# Sheet_Power.net
KiCad netlist of a schematic drawn in Altium Designer
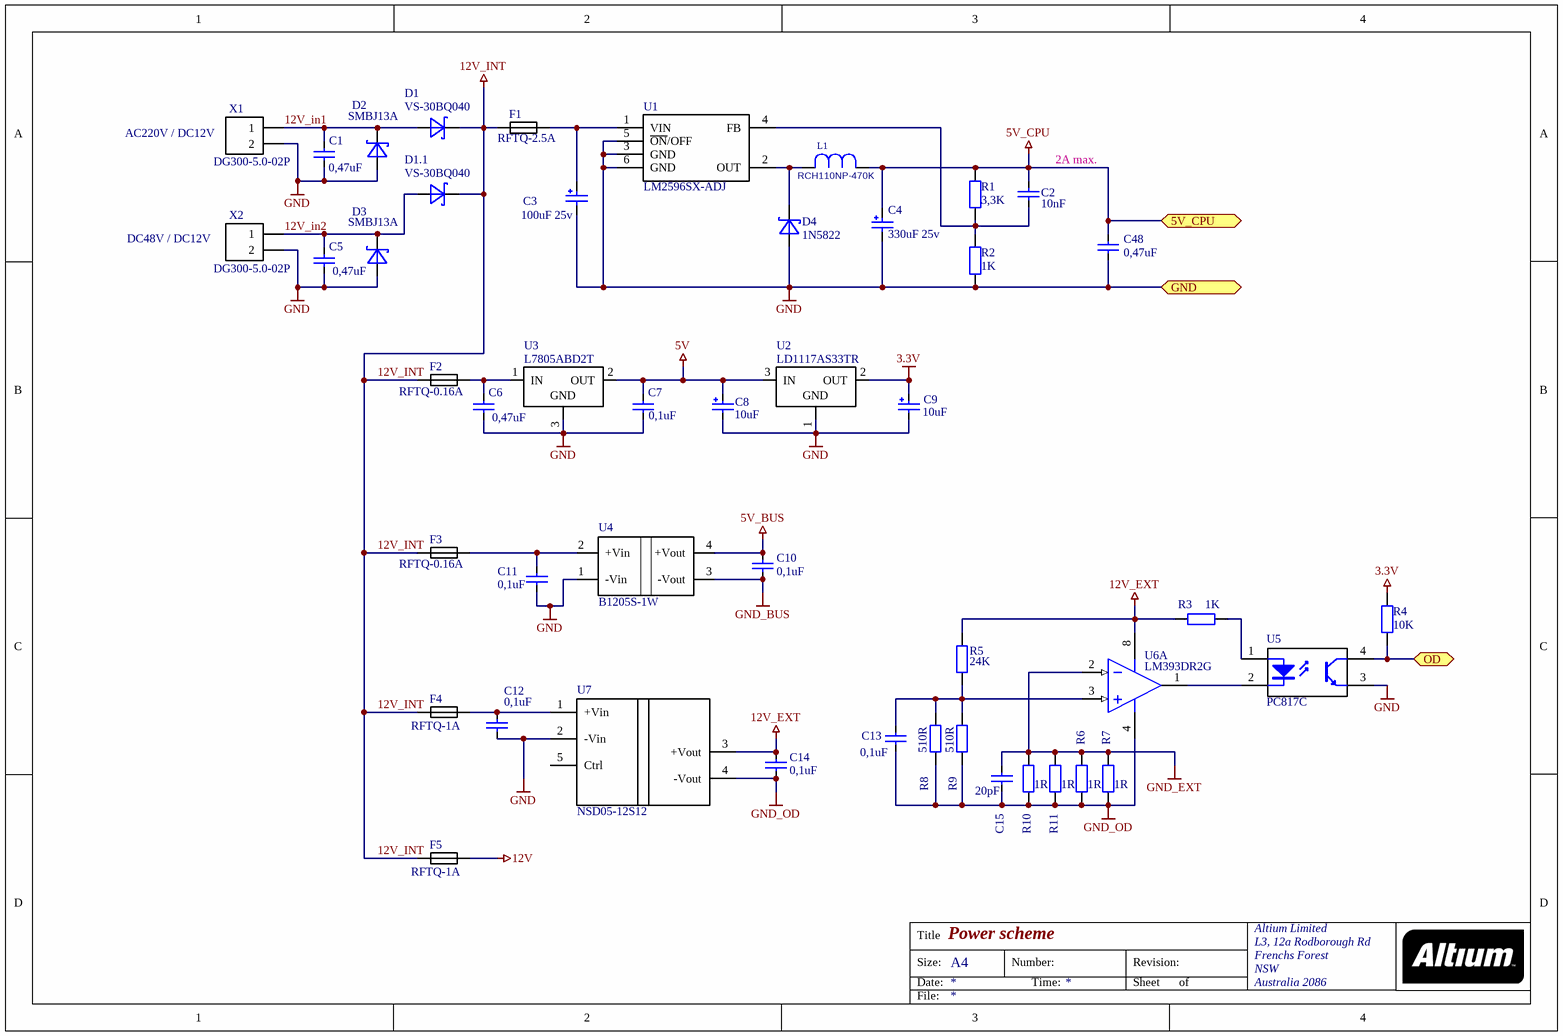
[diagram p0: Sheet_Power.SchDoc]

(export (version "E")
  (design (tool "Eeschema 10.0.6"))
  (components
    (comp (ref "C1")
      (value "0,47uF")
      (footprint "C_1206")
      (description "Capacitor semi")
      (fields (field (name "Comment") "Cap_Semi"))
      (libsource (lib "Capacitor") (part "Cap_Semi"))
    )
    (comp (ref "C2")
      (value "10nF")
      (footprint "C_0805")
      (description "Capacitor semi")
      (fields (field (name "Comment") "Cap_Semi"))
      (libsource (lib "Capacitor") (part "Cap_Semi"))
    )
    (comp (ref "C3")
      (value "100uF 25v")
      (footprint "8x11")
      (description "Capacitor Polar")
      (fields (field (name "Comment") "Cap_Polar"))
      (libsource (lib "Capacitor") (part "Cap_Polar"))
    )
    (comp (ref "C4")
      (value "330uF 25v")
      (footprint "10x16")
      (description "Capacitor Polar")
      (fields (field (name "Comment") "Cap_Polar"))
      (libsource (lib "Capacitor") (part "Cap_Polar"))
    )
    (comp (ref "C5")
      (value "0,47uF")
      (footprint "C_1206")
      (description "Capacitor semi")
      (fields (field (name "Comment") "Cap_Semi"))
      (libsource (lib "Capacitor") (part "Cap_Semi"))
    )
    (comp (ref "C6")
      (value "0,47uF")
      (footprint "C_1206")
      (description "Capacitor semi")
      (fields (field (name "Comment") "Cap_Semi"))
      (libsource (lib "Capacitor") (part "Cap_Semi"))
    )
    (comp (ref "C7")
      (value "0,1uF")
      (footprint "C_0805")
      (description "Capacitor semi")
      (fields (field (name "Comment") "Cap_Semi"))
      (libsource (lib "Capacitor") (part "Cap_Semi"))
    )
    (comp (ref "C8")
      (value "10uF")
      (footprint "5x11")
      (description "Capacitor polar")
      (fields (field (name "Comment") "Cap_Polar"))
      (libsource (lib "Capacitor") (part "Capacitor Polar"))
    )
    (comp (ref "C9")
      (value "10uF")
      (footprint "5x11")
      (description "Capacitor polar")
      (fields (field (name "Comment") "Cap_Polar"))
      (libsource (lib "Capacitor") (part "Capacitor Polar"))
    )
    (comp (ref "C10")
      (value "0,1uF")
      (footprint "C_0805")
      (description "Capacitor semi")
      (fields (field (name "Comment") "Cap_Semi"))
      (libsource (lib "Capacitor") (part "Cap_Semi"))
    )
    (comp (ref "C11")
      (value "0,1uF")
      (footprint "C_0805")
      (description "Capacitor semi")
      (fields (field (name "Comment") "Cap_Semi"))
      (libsource (lib "Capacitor") (part "Cap_Semi"))
    )
    (comp (ref "C12")
      (value "0,1uF")
      (footprint "C_0805")
      (description "Capacitor semi")
      (fields (field (name "Comment") "Cap_Semi"))
      (libsource (lib "Capacitor") (part "Cap_Semi"))
    )
    (comp (ref "C13")
      (value "0,1uF")
      (footprint "C_0805")
      (description "Capacitor semi")
      (fields (field (name "Comment") "Cap_Semi"))
      (libsource (lib "Capacitor") (part "Cap_Semi"))
    )
    (comp (ref "C14")
      (value "0,1uF")
      (footprint "C_0805")
      (description "Capacitor semi")
      (fields (field (name "Comment") "Cap_Semi"))
      (libsource (lib "Capacitor") (part "Cap_Semi"))
    )
    (comp (ref "C15")
      (value "20pF")
      (footprint "C_0805")
      (description "Capacitor semi")
      (fields (field (name "Comment") "Cap_Semi"))
      (libsource (lib "Capacitor") (part "Cap_Semi"))
    )
    (comp (ref "C48")
      (value "0,47uF")
      (footprint "C_1206")
      (description "Capacitor semi")
      (fields (field (name "Comment") "Cap_Semi"))
      (libsource (lib "Capacitor") (part "Cap_Semi"))
    )
    (comp (ref "D1")
      (value "VS-30BQ040")
      (footprint "SMC")
      (description "Diode Schottky")
      (libsource (lib "Diode") (part "VS-30BQ040"))
    )
    (comp (ref "D1.1")
      (value "VS-30BQ040")
      (footprint "SMC")
      (description "Diode Schottky")
      (libsource (lib "Diode") (part "VS-30BQ040"))
    )
    (comp (ref "D2")
      (value "SMBJ13A")
      (footprint "SMB")
      (description "Supressor")
      (libsource (lib "Diode") (part "SMBJ13A"))
    )
    (comp (ref "D3")
      (value "SMBJ13A")
      (footprint "SMB")
      (description "Supressor")
      (libsource (lib "Diode") (part "SMBJ13A"))
    )
    (comp (ref "D4")
      (value "1N5822")
      (footprint "DO-201")
      (description "Diode Schottky")
      (libsource (lib "Diode") (part "1N5822"))
    )
    (comp (ref "F1")
      (value "RFTQ-2.5A")
      (footprint "Fuse RFTQ")
      (description "Fuse")
      (libsource (lib "Other") (part "Fuse"))
    )
    (comp (ref "F2")
      (value "RFTQ-0.16A")
      (footprint "Fuse RFTQ")
      (description "Fuse")
      (libsource (lib "Other") (part "Fuse"))
    )
    (comp (ref "F3")
      (value "RFTQ-0.16A")
      (footprint "Fuse RFTQ")
      (description "Fuse")
      (libsource (lib "Other") (part "Fuse"))
    )
    (comp (ref "F4")
      (value "RFTQ-1A")
      (footprint "Fuse RFTQ")
      (description "Fuse")
      (libsource (lib "Other") (part "Fuse"))
    )
    (comp (ref "F5")
      (value "RFTQ-1A")
      (footprint "Fuse RFTQ")
      (description "Fuse")
      (libsource (lib "Other") (part "Fuse"))
    )
    (comp (ref "L1")
      (value "RCH110NP-470K")
      (footprint "RCH-110")
      (description "Inductor")
      (libsource (lib "Induction") (part "Inductor"))
    )
    (comp (ref "R1")
      (value "3,3K")
      (footprint "R_0805")
      (description "Resistor")
      (libsource (lib "Resistors") (part "Resistor"))
    )
    (comp (ref "R2")
      (value "1K")
      (footprint "R_0805")
      (description "Resistor")
      (libsource (lib "Resistors") (part "Resistor"))
    )
    (comp (ref "R3")
      (value "1K")
      (footprint "R_0805")
      (description "Resistor")
      (libsource (lib "") (part "Resistor_1"))
    )
    (comp (ref "R4")
      (value "10K")
      (footprint "R_0805")
      (description "Resistor")
      (libsource (lib "Resistors") (part "Resistor"))
    )
    (comp (ref "R5")
      (value "24K")
      (footprint "R_0805")
      (description "Resistor")
      (libsource (lib "Resistors") (part "Resistor"))
    )
    (comp (ref "R6")
      (value "1R")
      (footprint "R_1206")
      (description "Resistor")
      (libsource (lib "Resistors") (part "Resistor"))
    )
    (comp (ref "R7")
      (value "1R")
      (footprint "R_1206")
      (description "Resistor")
      (libsource (lib "Resistors") (part "Resistor"))
    )
    (comp (ref "R8")
      (value "510R")
      (footprint "R_0805")
      (description "Resistor")
      (libsource (lib "Resistors") (part "Resistor"))
    )
    (comp (ref "R9")
      (value "510R")
      (footprint "R_0805")
      (description "Resistor")
      (libsource (lib "Resistors") (part "Resistor"))
    )
    (comp (ref "R10")
      (value "1R")
      (footprint "R_1206")
      (description "Resistor")
      (libsource (lib "Resistors") (part "Resistor"))
    )
    (comp (ref "R11")
      (value "1R")
      (footprint "R_1206")
      (description "Resistor")
      (libsource (lib "Resistors") (part "Resistor"))
    )
    (comp (ref "U1")
      (value "LM2596SX-ADJ")
      (footprint "D2PAK_5p")
      (description "Easy Switcher 3.0A Step-Down Voltage Regulator")
      (libsource (lib "Power") (part "LM2596SX-ADJ"))
    )
    (comp (ref "U2")
      (value "LD1117AS33TR")
      (footprint "SOT-223_N")
      (description "Voltage Regulators 800mA")
      (libsource (lib "Power") (part "LD1117AS33TR"))
    )
    (comp (ref "U3")
      (value "L7805ABD2T")
      (footprint "D2PAK_3p")
      (description "Voltage Regulators")
      (libsource (lib "Power") (part "L7805ABD2T"))
    )
    (comp (ref "U4")
      (value "B1205S-1W")
      (footprint "SIP4")
      (description "DC/DC converter")
      (libsource (lib "Power") (part "B0505S-1W"))
    )
    (comp (ref "U5")
      (value "PC817C")
      (footprint "DIP-4")
      (description "Optocoupler")
      (libsource (lib "Chip_Packaging") (part "PC817"))
    )
    (comp (ref "U6")
      (value "LM393DR2G")
      (footprint "SO-8_L")
      (description "Dual Comparators")
      (libsource (lib "Chip_Packaging") (part "LM393DR2G"))
    )
    (comp (ref "U7")
      (value "NSD05-12S12")
      (footprint "NSD05")
      (description "DC/DC Regulated Single Output")
      (libsource (lib "Power") (part "NSD05-12S12"))
    )
    (comp (ref "X1")
      (value "DG300-5.0-02P")
      (footprint "5mm 2")
      (description "Connector 5mm")
      (fields (field (name "ALTIUM_UNNAMED_1") "DG300-5.0-02P"))
      (libsource (lib "Connect") (part "DG300_2pin"))
    )
    (comp (ref "X2")
      (value "DG300-5.0-02P")
      (footprint "5mm 2")
      (description "Connector 5mm")
      (fields (field (name "ALTIUM_UNNAMED_1") "DG300-5.0-02P"))
      (libsource (lib "Connect") (part "DG300_2pin"))
    )
  )
  (nets
    (net (code "1") (name "/12V_in1") (class "Default")
      (node (ref "C1") (pin "2") (pinfunction "2_2") (pintype "passive"))
      (node (ref "D1") (pin "1") (pinfunction "A_1") (pintype "passive"))
      (node (ref "D2") (pin "2") (pinfunction "C_2") (pintype "passive"))
      (node (ref "X1") (pin "1") (pinfunction "1_1") (pintype "passive"))
    )
    (net (code "2") (name "/12V_in2") (class "Default")
      (node (ref "C5") (pin "2") (pinfunction "2_2") (pintype "passive"))
      (node (ref "D1.1") (pin "1") (pinfunction "A_1") (pintype "passive"))
      (node (ref "D3") (pin "2") (pinfunction "C_2") (pintype "passive"))
      (node (ref "X2") (pin "1") (pinfunction "1_1") (pintype "passive"))
    )
    (net (code "3") (name "/OD") (class "Default")
      (node (ref "R4") (pin "1") (pinfunction "1_1") (pintype "passive"))
      (node (ref "U5") (pin "4") (pinfunction "C_4") (pintype "passive"))
    )
    (net (code "4") (name "3.3V") (class "Default")
      (node (ref "C9") (pin "1") (pinfunction "1_1") (pintype "passive"))
      (node (ref "R4") (pin "2") (pinfunction "2_2") (pintype "passive"))
      (node (ref "U2") (pin "2") (pinfunction "OUT_2") (pintype "power_in"))
    )
    (net (code "5") (name "5V") (class "Default")
      (node (ref "C7") (pin "2") (pinfunction "2_2") (pintype "passive"))
      (node (ref "C8") (pin "1") (pinfunction "1_1") (pintype "passive"))
      (node (ref "U2") (pin "3") (pinfunction "IN_3") (pintype "power_in"))
      (node (ref "U3") (pin "2") (pinfunction "OUT_2") (pintype "power_in"))
    )
    (net (code "6") (name "5V_BUS") (class "Default")
      (node (ref "C10") (pin "1") (pinfunction "1_1") (pintype "passive"))
      (node (ref "U4") (pin "4") (pinfunction "+Vout_4") (pintype "power_in"))
    )
    (net (code "7") (name "5V_CPU") (class "Default")
      (node (ref "C2") (pin "1") (pinfunction "1_1") (pintype "passive"))
      (node (ref "C4") (pin "1") (pinfunction "1_1") (pintype "passive"))
      (node (ref "C48") (pin "2") (pinfunction "2_2") (pintype "passive"))
      (node (ref "L1") (pin "1") (pintype "passive"))
      (node (ref "R1") (pin "2") (pinfunction "2_2") (pintype "passive"))
    )
    (net (code "8") (name "12V") (class "Default") (node (ref "F5") (pin "1") (pintype "passive")))
    (net (code "9") (name "12V_EXT") (class "Default")
      (node (ref "C14") (pin "2") (pinfunction "2_2") (pintype "passive"))
      (node (ref "R3") (pin "1") (pinfunction "1_1") (pintype "passive"))
      (node (ref "R5") (pin "2") (pinfunction "2_2") (pintype "passive"))
      (node (ref "U6") (pin "8") (pinfunction "VCC_8") (pintype "power_in"))
      (node (ref "U7") (pin "3") (pinfunction "+Vout_3") (pintype "power_in"))
    )
    (net (code "10") (name "12V_INT") (class "Default")
      (node (ref "D1") (pin "2") (pinfunction "C_2") (pintype "passive"))
      (node (ref "D1.1") (pin "2") (pinfunction "C_2") (pintype "passive"))
      (node (ref "F1") (pin "2") (pintype "passive"))
      (node (ref "F2") (pin "2") (pintype "passive"))
      (node (ref "F3") (pin "2") (pintype "passive"))
      (node (ref "F4") (pin "2") (pintype "passive"))
      (node (ref "F5") (pin "2") (pintype "passive"))
    )
    (net (code "11") (name "GND") (class "Default")
      (node (ref "C1") (pin "1") (pinfunction "1_1") (pintype "passive"))
      (node (ref "C11") (pin "2") (pinfunction "2_2") (pintype "passive"))
      (node (ref "C12") (pin "1") (pinfunction "1_1") (pintype "passive"))
      (node (ref "C3") (pin "2") (pinfunction "2_2") (pintype "passive"))
      (node (ref "C4") (pin "2") (pinfunction "2_2") (pintype "passive"))
      (node (ref "C48") (pin "1") (pinfunction "1_1") (pintype "passive"))
      (node (ref "C5") (pin "1") (pinfunction "1_1") (pintype "passive"))
      (node (ref "C6") (pin "1") (pinfunction "1_1") (pintype "passive"))
      (node (ref "C7") (pin "1") (pinfunction "1_1") (pintype "passive"))
      (node (ref "C8") (pin "2") (pinfunction "2_2") (pintype "passive"))
      (node (ref "C9") (pin "2") (pinfunction "2_2") (pintype "passive"))
      (node (ref "D2") (pin "1") (pinfunction "A_1") (pintype "passive"))
      (node (ref "D3") (pin "1") (pinfunction "A_1") (pintype "passive"))
      (node (ref "D4") (pin "1") (pinfunction "A_1") (pintype "passive"))
      (node (ref "R2") (pin "1") (pinfunction "1_1") (pintype "passive"))
      (node (ref "U1") (pin "3") (pinfunction "GND_3") (pintype "power_in"))
      (node (ref "U1") (pin "5") (pinfunction "~{ON}/OFF_5") (pintype "passive"))
      (node (ref "U1") (pin "6") (pinfunction "GND_6") (pintype "power_in"))
      (node (ref "U2") (pin "1") (pinfunction "GND_1") (pintype "power_in"))
      (node (ref "U3") (pin "3") (pinfunction "GND_3") (pintype "power_in"))
      (node (ref "U4") (pin "1") (pinfunction "-Vin_1") (pintype "power_in"))
      (node (ref "U5") (pin "3") (pinfunction "E_3") (pintype "passive"))
      (node (ref "U7") (pin "2") (pinfunction "-Vin_2") (pintype "power_in"))
      (node (ref "X1") (pin "2") (pinfunction "2_2") (pintype "passive"))
      (node (ref "X2") (pin "2") (pinfunction "2_2") (pintype "passive"))
    )
    (net (code "12") (name "GND_BUS") (class "Default")
      (node (ref "C10") (pin "2") (pinfunction "2_2") (pintype "passive"))
      (node (ref "U4") (pin "3") (pinfunction "-Vout_3") (pintype "power_in"))
    )
    (net (code "13") (name "GND_EXT") (class "Default")
      (node (ref "C15") (pin "2") (pinfunction "2_2") (pintype "passive"))
      (node (ref "R10") (pin "2") (pinfunction "2_2") (pintype "passive"))
      (node (ref "R11") (pin "2") (pinfunction "2_2") (pintype "passive"))
      (node (ref "R6") (pin "2") (pinfunction "2_2") (pintype "passive"))
      (node (ref "R7") (pin "2") (pinfunction "2_2") (pintype "passive"))
      (node (ref "U6") (pin "2") (pinfunction "INA-_2") (pintype "input"))
    )
    (net (code "14") (name "GND_OD") (class "Default")
      (node (ref "C13") (pin "1") (pinfunction "1_1") (pintype "passive"))
      (node (ref "C14") (pin "1") (pinfunction "1_1") (pintype "passive"))
      (node (ref "C15") (pin "1") (pinfunction "1_1") (pintype "passive"))
      (node (ref "R10") (pin "1") (pinfunction "1_1") (pintype "passive"))
      (node (ref "R11") (pin "1") (pinfunction "1_1") (pintype "passive"))
      (node (ref "R6") (pin "1") (pinfunction "1_1") (pintype "passive"))
      (node (ref "R7") (pin "1") (pinfunction "1_1") (pintype "passive"))
      (node (ref "R8") (pin "1") (pinfunction "1_1") (pintype "passive"))
      (node (ref "R9") (pin "1") (pinfunction "1_1") (pintype "passive"))
      (node (ref "U6") (pin "4") (pinfunction "GND_4") (pintype "power_in"))
      (node (ref "U7") (pin "4") (pinfunction "-Vout_4") (pintype "power_in"))
    )
    (net (code "15") (name "Net-(D4-C)") (class "Default")
      (node (ref "D4") (pin "2") (pinfunction "C_2") (pintype "passive"))
      (node (ref "L1") (pin "2") (pintype "passive"))
      (node (ref "U1") (pin "2") (pinfunction "OUT_2") (pintype "open_emitter"))
    )
    (net (code "16") (name "Net-(U1-FB)") (class "Default")
      (node (ref "C2") (pin "2") (pinfunction "2_2") (pintype "passive"))
      (node (ref "R1") (pin "1") (pinfunction "1_1") (pintype "passive"))
      (node (ref "R2") (pin "2") (pinfunction "2_2") (pintype "passive"))
      (node (ref "U1") (pin "4") (pinfunction "FB_4") (pintype "passive"))
    )
    (net (code "17") (name "Net-(U1-VIN)") (class "Default")
      (node (ref "C3") (pin "1") (pinfunction "1_1") (pintype "passive"))
      (node (ref "F1") (pin "1") (pintype "passive"))
      (node (ref "U1") (pin "1") (pinfunction "VIN_1") (pintype "power_in"))
    )
    (net (code "18") (name "Net-(U3-IN)") (class "Default")
      (node (ref "C6") (pin "2") (pinfunction "2_2") (pintype "passive"))
      (node (ref "F2") (pin "1") (pintype "passive"))
      (node (ref "U3") (pin "1") (pinfunction "IN_1") (pintype "power_in"))
    )
    (net (code "19") (name "Net-(U4-+Vin)") (class "Default")
      (node (ref "C11") (pin "1") (pinfunction "1_1") (pintype "passive"))
      (node (ref "F3") (pin "1") (pintype "passive"))
      (node (ref "U4") (pin "2") (pinfunction "+Vin_2") (pintype "power_in"))
    )
    (net (code "20") (name "Net-(U5-A)") (class "Default")
      (node (ref "R3") (pin "2") (pinfunction "2_2") (pintype "passive"))
      (node (ref "U5") (pin "1") (pinfunction "A_1") (pintype "passive"))
    )
    (net (code "21") (name "Net-(U5-K)") (class "Default")
      (node (ref "U5") (pin "2") (pinfunction "K_2") (pintype "passive"))
      (node (ref "U6") (pin "1") (pinfunction "OUTA_1") (pintype "open_collector"))
    )
    (net (code "22") (name "Net-(U6A-INA+)") (class "Default")
      (node (ref "C13") (pin "2") (pinfunction "2_2") (pintype "passive"))
      (node (ref "R5") (pin "1") (pinfunction "1_1") (pintype "passive"))
      (node (ref "R8") (pin "2") (pinfunction "2_2") (pintype "passive"))
      (node (ref "R9") (pin "2") (pinfunction "2_2") (pintype "passive"))
      (node (ref "U6") (pin "3") (pinfunction "INA+_3") (pintype "input"))
    )
    (net (code "23") (name "Net-(U7-+Vin)") (class "Default")
      (node (ref "C12") (pin "2") (pinfunction "2_2") (pintype "passive"))
      (node (ref "F4") (pin "1") (pintype "passive"))
      (node (ref "U7") (pin "1") (pinfunction "+Vin_1") (pintype "power_in"))
    )
    (net (code "24") (name "unconnected-(U7-Ctrl-Pad5)") (class "Default")
      (node (ref "U7") (pin "5") (pinfunction "Ctrl_5") (pintype "passive"))
    )
  )
)
